# single_ad8232_d1.net
KiCad netlist of a schematic drawn in EAGLE
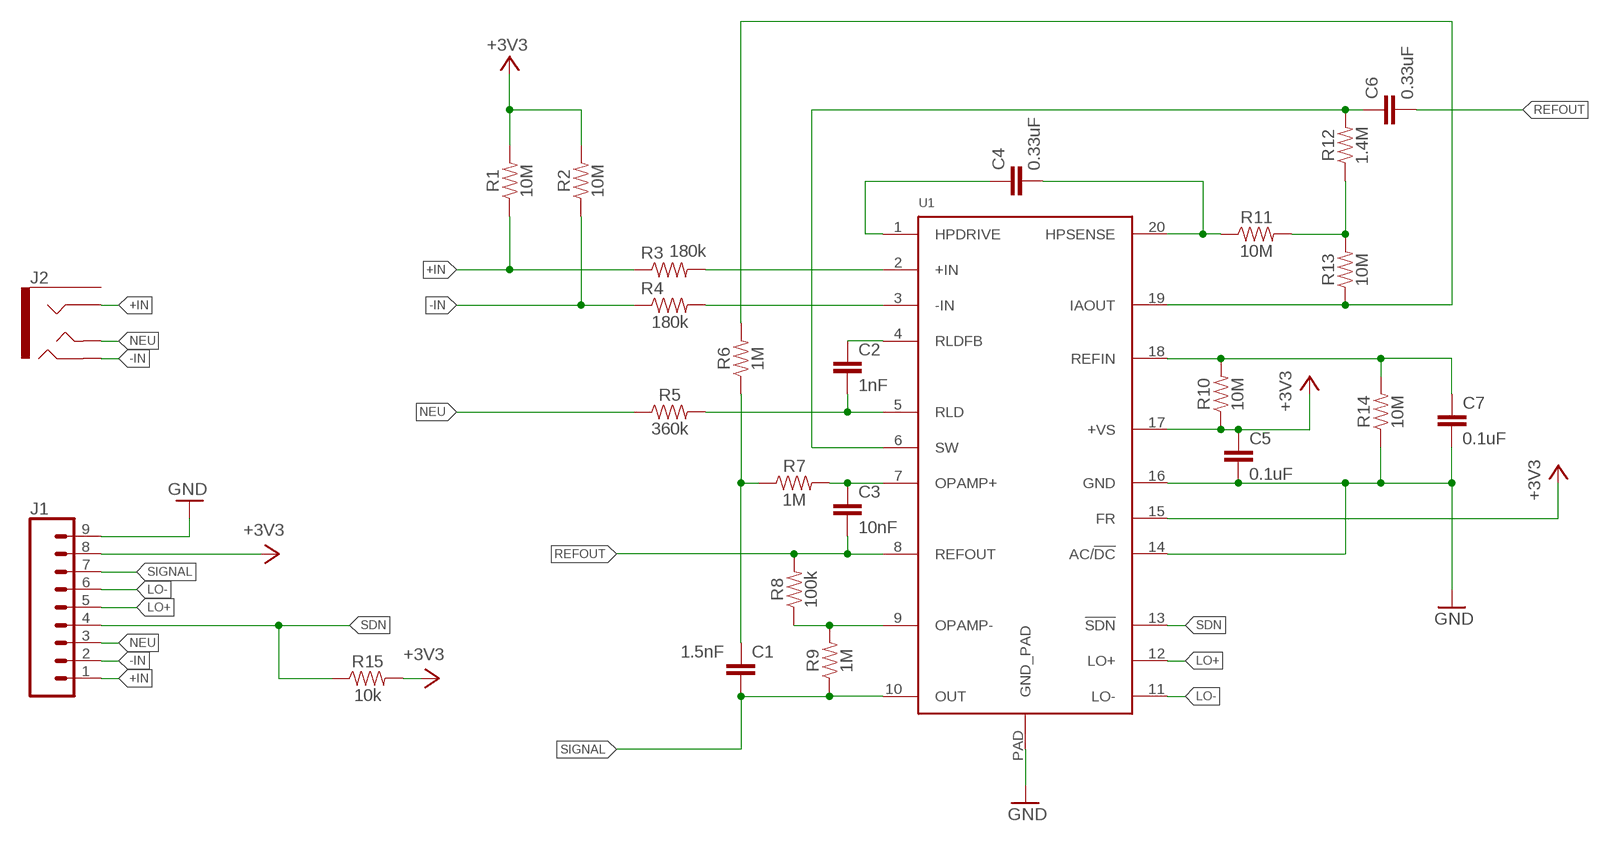
[diagram p0: schematic, sheet 1]

(export (version "E")
  (design (tool "Eeschema 10.0.6"))
  (components
    (comp (ref "C1")
      (value "1.5nF")
      (footprint "eagle-import:0603-CAP")
      (libsource (lib "eagle-import") (part "CAP0603-CAP"))
    )
    (comp (ref "C2")
      (value "1nF")
      (footprint "eagle-import:0603-CAP")
      (libsource (lib "eagle-import") (part "CAP0603-CAP"))
    )
    (comp (ref "C3")
      (value "10nF")
      (footprint "eagle-import:0603-CAP")
      (libsource (lib "eagle-import") (part "CAP0603-CAP"))
    )
    (comp (ref "C4")
      (value "0.33uF")
      (footprint "eagle-import:0805")
      (libsource (lib "eagle-import") (part "CAP0805"))
    )
    (comp (ref "C5")
      (value "0.1uF")
      (footprint "eagle-import:0603-CAP")
      (libsource (lib "eagle-import") (part "CAP0603-CAP"))
    )
    (comp (ref "C6")
      (value "0.33uF")
      (footprint "eagle-import:0805")
      (libsource (lib "eagle-import") (part "CAP0805"))
    )
    (comp (ref "C7")
      (value "0.1uF")
      (footprint "eagle-import:0603-CAP")
      (libsource (lib "eagle-import") (part "CAP0603-CAP"))
    )
    (comp (ref "J1")
      (value "CONN_09")
      (footprint "eagle-import:1X09")
      (libsource (lib "eagle-import") (part "CONN_09"))
    )
    (comp (ref "J2")
      (value "AUDIO_JACK_TRRSSMD_RA")
      (footprint "eagle-import:AUDIO_JACK_3.5MM_TRRS_SMD_RA")
      (libsource (lib "eagle-import") (part "AUDIO_JACK_TRRSSMD_RA"))
    )
    (comp (ref "R1")
      (value "10M")
      (footprint "eagle-import:0603")
      (libsource (lib "eagle-import") (part "RESISTOR0603"))
    )
    (comp (ref "R2")
      (value "10M")
      (footprint "eagle-import:0603")
      (libsource (lib "eagle-import") (part "RESISTOR0603"))
    )
    (comp (ref "R3")
      (value "180k")
      (footprint "eagle-import:0603")
      (libsource (lib "eagle-import") (part "RESISTOR0603"))
    )
    (comp (ref "R4")
      (value "180k")
      (footprint "eagle-import:0603")
      (libsource (lib "eagle-import") (part "RESISTOR0603"))
    )
    (comp (ref "R5")
      (value "360k")
      (footprint "eagle-import:0603")
      (libsource (lib "eagle-import") (part "RESISTOR0603"))
    )
    (comp (ref "R6")
      (value "1M")
      (footprint "eagle-import:0603")
      (libsource (lib "eagle-import") (part "RESISTOR0603"))
    )
    (comp (ref "R7")
      (value "1M")
      (footprint "eagle-import:0603")
      (libsource (lib "eagle-import") (part "RESISTOR0603"))
    )
    (comp (ref "R8")
      (value "100k")
      (footprint "eagle-import:0603")
      (libsource (lib "eagle-import") (part "RESISTOR0603"))
    )
    (comp (ref "R9")
      (value "1M")
      (footprint "eagle-import:0603")
      (libsource (lib "eagle-import") (part "RESISTOR0603"))
    )
    (comp (ref "R10")
      (value "10M")
      (footprint "eagle-import:0603")
      (libsource (lib "eagle-import") (part "RESISTOR0603"))
    )
    (comp (ref "R11")
      (value "10M")
      (footprint "eagle-import:0603")
      (libsource (lib "eagle-import") (part "RESISTOR0603"))
    )
    (comp (ref "R12")
      (value "1.4M")
      (footprint "eagle-import:0603")
      (libsource (lib "eagle-import") (part "RESISTOR0603"))
    )
    (comp (ref "R13")
      (value "10M")
      (footprint "eagle-import:0603")
      (libsource (lib "eagle-import") (part "RESISTOR0603"))
    )
    (comp (ref "R14")
      (value "10M")
      (footprint "eagle-import:0603")
      (libsource (lib "eagle-import") (part "RESISTOR0603"))
    )
    (comp (ref "R15")
      (value "10k")
      (footprint "eagle-import:0603")
      (libsource (lib "eagle-import") (part "10KOHM-0603-1/10W-1%"))
    )
    (comp (ref "U1")
      (value "AD8232ACPZ-R7")
      (footprint "eagle-import:LFCSP_20")
      (libsource (lib "eagle-import") (part "AD8232"))
    )
  )
  (nets
    (net (code "1") (name "+3V3") (class "Default")
      (node (ref "C5") (pin "1") (pinfunction "1_1") (pintype "passive"))
      (node (ref "J1") (pin "8") (pinfunction "8_8") (pintype "passive"))
      (node (ref "R1") (pin "2") (pinfunction "2_2") (pintype "passive"))
      (node (ref "R10") (pin "1") (pinfunction "1_1") (pintype "passive"))
      (node (ref "R15") (pin "2") (pinfunction "2_2") (pintype "passive"))
      (node (ref "R2") (pin "2") (pinfunction "2_2") (pintype "passive"))
      (node (ref "U1") (pin "15") (pinfunction "FR_15") (pintype "bidirectional"))
      (node (ref "U1") (pin "17") (pinfunction "+VS_17") (pintype "bidirectional"))
    )
    (net (code "2") (name "+IN") (class "Default")
      (node (ref "J1") (pin "1") (pinfunction "1_1") (pintype "passive"))
      (node (ref "J2") (pin "RING1") (pinfunction "RING1_RING1") (pintype "bidirectional"))
      (node (ref "R1") (pin "1") (pinfunction "1_1") (pintype "passive"))
      (node (ref "R3") (pin "1") (pinfunction "1_1") (pintype "passive"))
    )
    (net (code "3") (name "-IN") (class "Default")
      (node (ref "J1") (pin "2") (pinfunction "2_2") (pintype "passive"))
      (node (ref "J2") (pin "RING2") (pinfunction "RING2_RING2") (pintype "bidirectional"))
      (node (ref "R2") (pin "1") (pinfunction "1_1") (pintype "passive"))
      (node (ref "R4") (pin "1") (pinfunction "1_1") (pintype "passive"))
    )
    (net (code "4") (name "GND") (class "Default")
      (node (ref "C5") (pin "2") (pinfunction "2_2") (pintype "passive"))
      (node (ref "C7") (pin "2") (pinfunction "2_2") (pintype "passive"))
      (node (ref "J1") (pin "9") (pinfunction "9_9") (pintype "passive"))
      (node (ref "R14") (pin "1") (pinfunction "1_1") (pintype "passive"))
      (node (ref "U1") (pin "14") (pinfunction "AC/~{DC}_14") (pintype "bidirectional"))
      (node (ref "U1") (pin "16") (pinfunction "GND_16") (pintype "bidirectional"))
      (node (ref "U1") (pin "PAD") (pinfunction "GND_PAD_PAD") (pintype "bidirectional"))
    )
    (net (code "5") (name "LO+") (class "Default")
      (node (ref "J1") (pin "5") (pinfunction "5_5") (pintype "passive"))
      (node (ref "U1") (pin "12") (pinfunction "LO+_12") (pintype "bidirectional"))
    )
    (net (code "6") (name "LO-") (class "Default")
      (node (ref "J1") (pin "6") (pinfunction "6_6") (pintype "passive"))
      (node (ref "U1") (pin "11") (pinfunction "LO-_11") (pintype "bidirectional"))
    )
    (net (code "7") (name "NEU") (class "Default")
      (node (ref "J1") (pin "3") (pinfunction "3_3") (pintype "passive"))
      (node (ref "J2") (pin "TIP") (pinfunction "TIP_TIP") (pintype "bidirectional"))
      (node (ref "R5") (pin "1") (pinfunction "1_1") (pintype "passive"))
    )
    (net (code "8") (name "Net-(C1-Pad1)") (class "Default")
      (node (ref "C1") (pin "1") (pinfunction "1_1") (pintype "passive"))
      (node (ref "R6") (pin "1") (pinfunction "1_1") (pintype "passive"))
      (node (ref "R7") (pin "1") (pinfunction "1_1") (pintype "passive"))
    )
    (net (code "9") (name "Net-(R11-Pad2)") (class "Default")
      (node (ref "R11") (pin "2") (pinfunction "2_2") (pintype "passive"))
      (node (ref "R12") (pin "1") (pinfunction "1_1") (pintype "passive"))
      (node (ref "R13") (pin "2") (pinfunction "2_2") (pintype "passive"))
    )
    (net (code "10") (name "Net-(U1-+IN)") (class "Default")
      (node (ref "R3") (pin "2") (pinfunction "2_2") (pintype "passive"))
      (node (ref "U1") (pin "2") (pinfunction "+IN_2") (pintype "bidirectional"))
    )
    (net (code "11") (name "Net-(U1--IN)") (class "Default")
      (node (ref "R4") (pin "2") (pinfunction "2_2") (pintype "passive"))
      (node (ref "U1") (pin "3") (pinfunction "-IN_3") (pintype "bidirectional"))
    )
    (net (code "12") (name "Net-(U1-HPDRIVE)") (class "Default")
      (node (ref "C4") (pin "1") (pinfunction "1_1") (pintype "passive"))
      (node (ref "U1") (pin "1") (pinfunction "HPDRIVE_1") (pintype "bidirectional"))
    )
    (net (code "13") (name "Net-(U1-HPSENSE)") (class "Default")
      (node (ref "C4") (pin "2") (pinfunction "2_2") (pintype "passive"))
      (node (ref "R11") (pin "1") (pinfunction "1_1") (pintype "passive"))
      (node (ref "U1") (pin "20") (pinfunction "HPSENSE_20") (pintype "bidirectional"))
    )
    (net (code "14") (name "Net-(U1-IAOUT)") (class "Default")
      (node (ref "R13") (pin "1") (pinfunction "1_1") (pintype "passive"))
      (node (ref "R6") (pin "2") (pinfunction "2_2") (pintype "passive"))
      (node (ref "U1") (pin "19") (pinfunction "IAOUT_19") (pintype "bidirectional"))
    )
    (net (code "15") (name "Net-(U1-OPAMP+)") (class "Default")
      (node (ref "C3") (pin "1") (pinfunction "1_1") (pintype "passive"))
      (node (ref "R7") (pin "2") (pinfunction "2_2") (pintype "passive"))
      (node (ref "U1") (pin "7") (pinfunction "OPAMP+_7") (pintype "bidirectional"))
    )
    (net (code "16") (name "Net-(U1-OPAMP-)") (class "Default")
      (node (ref "R8") (pin "1") (pinfunction "1_1") (pintype "passive"))
      (node (ref "R9") (pin "2") (pinfunction "2_2") (pintype "passive"))
      (node (ref "U1") (pin "9") (pinfunction "OPAMP-_9") (pintype "bidirectional"))
    )
    (net (code "17") (name "Net-(U1-REFIN)") (class "Default")
      (node (ref "C7") (pin "1") (pinfunction "1_1") (pintype "passive"))
      (node (ref "R10") (pin "2") (pinfunction "2_2") (pintype "passive"))
      (node (ref "R14") (pin "2") (pinfunction "2_2") (pintype "passive"))
      (node (ref "U1") (pin "18") (pinfunction "REFIN_18") (pintype "bidirectional"))
    )
    (net (code "18") (name "Net-(U1-RLD)") (class "Default")
      (node (ref "C2") (pin "2") (pinfunction "2_2") (pintype "passive"))
      (node (ref "R5") (pin "2") (pinfunction "2_2") (pintype "passive"))
      (node (ref "U1") (pin "5") (pinfunction "RLD_5") (pintype "bidirectional"))
    )
    (net (code "19") (name "Net-(U1-RLDFB)") (class "Default")
      (node (ref "C2") (pin "1") (pinfunction "1_1") (pintype "passive"))
      (node (ref "U1") (pin "4") (pinfunction "RLDFB_4") (pintype "bidirectional"))
    )
    (net (code "20") (name "Net-(U1-SW)") (class "Default")
      (node (ref "C6") (pin "1") (pinfunction "1_1") (pintype "passive"))
      (node (ref "R12") (pin "2") (pinfunction "2_2") (pintype "passive"))
      (node (ref "U1") (pin "6") (pinfunction "SW_6") (pintype "bidirectional"))
    )
    (net (code "21") (name "REFOUT") (class "Default")
      (node (ref "C3") (pin "2") (pinfunction "2_2") (pintype "passive"))
      (node (ref "C6") (pin "2") (pinfunction "2_2") (pintype "passive"))
      (node (ref "R8") (pin "2") (pinfunction "2_2") (pintype "passive"))
      (node (ref "U1") (pin "8") (pinfunction "REFOUT_8") (pintype "bidirectional"))
    )
    (net (code "22") (name "SDN") (class "Default")
      (node (ref "J1") (pin "4") (pinfunction "4_4") (pintype "passive"))
      (node (ref "R15") (pin "1") (pinfunction "1_1") (pintype "passive"))
      (node (ref "U1") (pin "13") (pinfunction "~{SDN}_13") (pintype "bidirectional"))
    )
    (net (code "23") (name "SIGNAL") (class "Default")
      (node (ref "C1") (pin "2") (pinfunction "2_2") (pintype "passive"))
      (node (ref "J1") (pin "7") (pinfunction "7_7") (pintype "passive"))
      (node (ref "R9") (pin "1") (pinfunction "1_1") (pintype "passive"))
      (node (ref "U1") (pin "10") (pinfunction "OUT_10") (pintype "bidirectional"))
    )
    (net (code "24") (name "unconnected-(J2-PadEARTH)") (class "Default")
      (node (ref "J2") (pin "EARTH") (pinfunction "EARTH_EARTH") (pintype "bidirectional"))
    )
  )
)
